# wordclock-ledboard.net
KiCad netlist of a schematic drawn in EAGLE
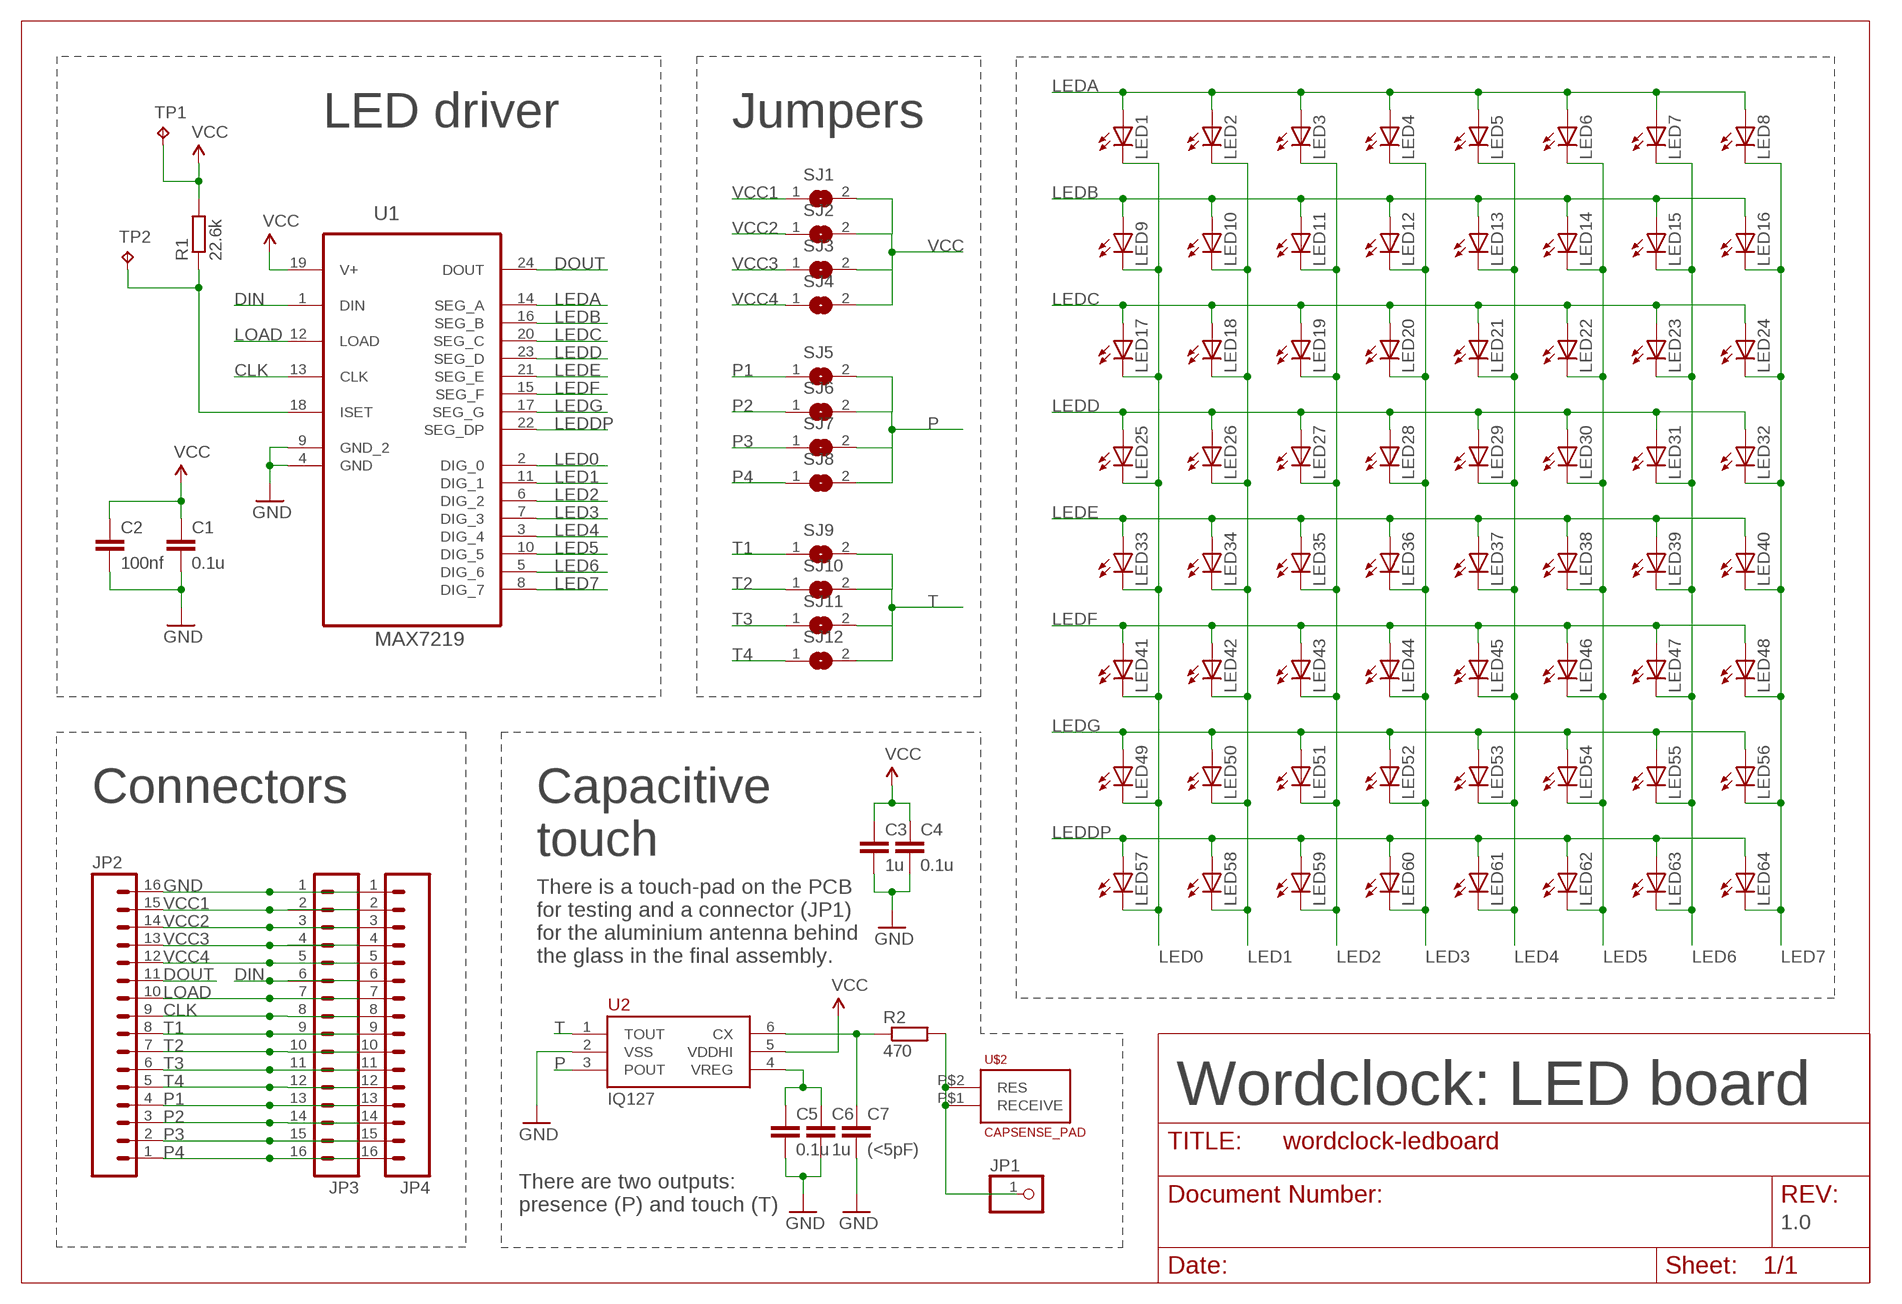
[diagram p0: schematic, sheet 1]

(export (version "E")
  (design (tool "Eeschema 10.0.6"))
  (components
    (comp (ref "C1")
      (value "0.1u")
      (footprint "eagle-import:C0805")
      (libsource (lib "eagle-import") (part "C-EUC0805"))
    )
    (comp (ref "C2")
      (value "100nf")
      (footprint "eagle-import:C0805")
      (libsource (lib "eagle-import") (part "C-EUC0805"))
    )
    (comp (ref "C3")
      (value "1u")
      (footprint "eagle-import:C0805")
      (libsource (lib "eagle-import") (part "C-EUC0805"))
    )
    (comp (ref "C4")
      (value "0.1u")
      (footprint "eagle-import:C0805")
      (libsource (lib "eagle-import") (part "C-EUC0805"))
    )
    (comp (ref "C5")
      (value "0.1u")
      (footprint "eagle-import:C0805")
      (libsource (lib "eagle-import") (part "C-EUC0805"))
    )
    (comp (ref "C6")
      (value "1u")
      (footprint "eagle-import:C0805")
      (libsource (lib "eagle-import") (part "C-EUC0805"))
    )
    (comp (ref "C7")
      (value "(<5pF)")
      (footprint "eagle-import:C0805")
      (libsource (lib "eagle-import") (part "C-EUC0805"))
    )
    (comp (ref "JP1")
      (value "PINHD-1X1")
      (footprint "eagle-import:1X01")
      (libsource (lib "eagle-import") (part "PINHD-1X1"))
    )
    (comp (ref "JP2")
      (value "M161X16_NO_SILK")
      (footprint "eagle-import:1X16_NO_SILK")
      (libsource (lib "eagle-import") (part "M161X16_NO_SILK"))
    )
    (comp (ref "JP3")
      (value "M161X16_NO_SILK")
      (footprint "eagle-import:1X16_NO_SILK")
      (libsource (lib "eagle-import") (part "M161X16_NO_SILK"))
    )
    (comp (ref "JP4")
      (value "M161X16_NO_SILK")
      (footprint "eagle-import:1X16_NO_SILK")
      (libsource (lib "eagle-import") (part "M161X16_NO_SILK"))
    )
    (comp (ref "LED1")
      (value "LEDKA-3528ASYC")
      (footprint "eagle-import:KA-3528ASYC")
      (libsource (lib "eagle-import") (part "LEDKA-3528ASYC"))
    )
    (comp (ref "LED2")
      (value "LEDKA-3528ASYC")
      (footprint "eagle-import:KA-3528ASYC")
      (libsource (lib "eagle-import") (part "LEDKA-3528ASYC"))
    )
    (comp (ref "LED3")
      (value "LEDKA-3528ASYC")
      (footprint "eagle-import:KA-3528ASYC")
      (libsource (lib "eagle-import") (part "LEDKA-3528ASYC"))
    )
    (comp (ref "LED4")
      (value "LEDKA-3528ASYC")
      (footprint "eagle-import:KA-3528ASYC")
      (libsource (lib "eagle-import") (part "LEDKA-3528ASYC"))
    )
    (comp (ref "LED5")
      (value "LEDKA-3528ASYC")
      (footprint "eagle-import:KA-3528ASYC")
      (libsource (lib "eagle-import") (part "LEDKA-3528ASYC"))
    )
    (comp (ref "LED6")
      (value "LEDKA-3528ASYC")
      (footprint "eagle-import:KA-3528ASYC")
      (libsource (lib "eagle-import") (part "LEDKA-3528ASYC"))
    )
    (comp (ref "LED7")
      (value "LEDKA-3528ASYC")
      (footprint "eagle-import:KA-3528ASYC")
      (libsource (lib "eagle-import") (part "LEDKA-3528ASYC"))
    )
    (comp (ref "LED8")
      (value "LEDKA-3528ASYC")
      (footprint "eagle-import:KA-3528ASYC")
      (libsource (lib "eagle-import") (part "LEDKA-3528ASYC"))
    )
    (comp (ref "LED9")
      (value "LEDKA-3528ASYC")
      (footprint "eagle-import:KA-3528ASYC")
      (libsource (lib "eagle-import") (part "LEDKA-3528ASYC"))
    )
    (comp (ref "LED10")
      (value "LEDKA-3528ASYC")
      (footprint "eagle-import:KA-3528ASYC")
      (libsource (lib "eagle-import") (part "LEDKA-3528ASYC"))
    )
    (comp (ref "LED11")
      (value "LEDKA-3528ASYC")
      (footprint "eagle-import:KA-3528ASYC")
      (libsource (lib "eagle-import") (part "LEDKA-3528ASYC"))
    )
    (comp (ref "LED12")
      (value "LEDKA-3528ASYC")
      (footprint "eagle-import:KA-3528ASYC")
      (libsource (lib "eagle-import") (part "LEDKA-3528ASYC"))
    )
    (comp (ref "LED13")
      (value "LEDKA-3528ASYC")
      (footprint "eagle-import:KA-3528ASYC")
      (libsource (lib "eagle-import") (part "LEDKA-3528ASYC"))
    )
    (comp (ref "LED14")
      (value "LEDKA-3528ASYC")
      (footprint "eagle-import:KA-3528ASYC")
      (libsource (lib "eagle-import") (part "LEDKA-3528ASYC"))
    )
    (comp (ref "LED15")
      (value "LEDKA-3528ASYC")
      (footprint "eagle-import:KA-3528ASYC")
      (libsource (lib "eagle-import") (part "LEDKA-3528ASYC"))
    )
    (comp (ref "LED16")
      (value "LEDKA-3528ASYC")
      (footprint "eagle-import:KA-3528ASYC")
      (libsource (lib "eagle-import") (part "LEDKA-3528ASYC"))
    )
    (comp (ref "LED17")
      (value "LEDKA-3528ASYC")
      (footprint "eagle-import:KA-3528ASYC")
      (libsource (lib "eagle-import") (part "LEDKA-3528ASYC"))
    )
    (comp (ref "LED18")
      (value "LEDKA-3528ASYC")
      (footprint "eagle-import:KA-3528ASYC")
      (libsource (lib "eagle-import") (part "LEDKA-3528ASYC"))
    )
    (comp (ref "LED19")
      (value "LEDKA-3528ASYC")
      (footprint "eagle-import:KA-3528ASYC")
      (libsource (lib "eagle-import") (part "LEDKA-3528ASYC"))
    )
    (comp (ref "LED20")
      (value "LEDKA-3528ASYC")
      (footprint "eagle-import:KA-3528ASYC")
      (libsource (lib "eagle-import") (part "LEDKA-3528ASYC"))
    )
    (comp (ref "LED21")
      (value "LEDKA-3528ASYC")
      (footprint "eagle-import:KA-3528ASYC")
      (libsource (lib "eagle-import") (part "LEDKA-3528ASYC"))
    )
    (comp (ref "LED22")
      (value "LEDKA-3528ASYC")
      (footprint "eagle-import:KA-3528ASYC")
      (libsource (lib "eagle-import") (part "LEDKA-3528ASYC"))
    )
    (comp (ref "LED23")
      (value "LEDKA-3528ASYC")
      (footprint "eagle-import:KA-3528ASYC")
      (libsource (lib "eagle-import") (part "LEDKA-3528ASYC"))
    )
    (comp (ref "LED24")
      (value "LEDKA-3528ASYC")
      (footprint "eagle-import:KA-3528ASYC")
      (libsource (lib "eagle-import") (part "LEDKA-3528ASYC"))
    )
    (comp (ref "LED25")
      (value "LEDKA-3528ASYC")
      (footprint "eagle-import:KA-3528ASYC")
      (libsource (lib "eagle-import") (part "LEDKA-3528ASYC"))
    )
    (comp (ref "LED26")
      (value "LEDKA-3528ASYC")
      (footprint "eagle-import:KA-3528ASYC")
      (libsource (lib "eagle-import") (part "LEDKA-3528ASYC"))
    )
    (comp (ref "LED27")
      (value "LEDKA-3528ASYC")
      (footprint "eagle-import:KA-3528ASYC")
      (libsource (lib "eagle-import") (part "LEDKA-3528ASYC"))
    )
    (comp (ref "LED28")
      (value "LEDKA-3528ASYC")
      (footprint "eagle-import:KA-3528ASYC")
      (libsource (lib "eagle-import") (part "LEDKA-3528ASYC"))
    )
    (comp (ref "LED29")
      (value "LEDKA-3528ASYC")
      (footprint "eagle-import:KA-3528ASYC")
      (libsource (lib "eagle-import") (part "LEDKA-3528ASYC"))
    )
    (comp (ref "LED30")
      (value "LEDKA-3528ASYC")
      (footprint "eagle-import:KA-3528ASYC")
      (libsource (lib "eagle-import") (part "LEDKA-3528ASYC"))
    )
    (comp (ref "LED31")
      (value "LEDKA-3528ASYC")
      (footprint "eagle-import:KA-3528ASYC")
      (libsource (lib "eagle-import") (part "LEDKA-3528ASYC"))
    )
    (comp (ref "LED32")
      (value "LEDKA-3528ASYC")
      (footprint "eagle-import:KA-3528ASYC")
      (libsource (lib "eagle-import") (part "LEDKA-3528ASYC"))
    )
    (comp (ref "LED33")
      (value "LEDKA-3528ASYC")
      (footprint "eagle-import:KA-3528ASYC")
      (libsource (lib "eagle-import") (part "LEDKA-3528ASYC"))
    )
    (comp (ref "LED34")
      (value "LEDKA-3528ASYC")
      (footprint "eagle-import:KA-3528ASYC")
      (libsource (lib "eagle-import") (part "LEDKA-3528ASYC"))
    )
    (comp (ref "LED35")
      (value "LEDKA-3528ASYC")
      (footprint "eagle-import:KA-3528ASYC")
      (libsource (lib "eagle-import") (part "LEDKA-3528ASYC"))
    )
    (comp (ref "LED36")
      (value "LEDKA-3528ASYC")
      (footprint "eagle-import:KA-3528ASYC")
      (libsource (lib "eagle-import") (part "LEDKA-3528ASYC"))
    )
    (comp (ref "LED37")
      (value "LEDKA-3528ASYC")
      (footprint "eagle-import:KA-3528ASYC")
      (libsource (lib "eagle-import") (part "LEDKA-3528ASYC"))
    )
    (comp (ref "LED38")
      (value "LEDKA-3528ASYC")
      (footprint "eagle-import:KA-3528ASYC")
      (libsource (lib "eagle-import") (part "LEDKA-3528ASYC"))
    )
    (comp (ref "LED39")
      (value "LEDKA-3528ASYC")
      (footprint "eagle-import:KA-3528ASYC")
      (libsource (lib "eagle-import") (part "LEDKA-3528ASYC"))
    )
    (comp (ref "LED40")
      (value "LEDKA-3528ASYC")
      (footprint "eagle-import:KA-3528ASYC")
      (libsource (lib "eagle-import") (part "LEDKA-3528ASYC"))
    )
    (comp (ref "LED41")
      (value "LEDKA-3528ASYC")
      (footprint "eagle-import:KA-3528ASYC")
      (libsource (lib "eagle-import") (part "LEDKA-3528ASYC"))
    )
    (comp (ref "LED42")
      (value "LEDKA-3528ASYC")
      (footprint "eagle-import:KA-3528ASYC")
      (libsource (lib "eagle-import") (part "LEDKA-3528ASYC"))
    )
    (comp (ref "LED43")
      (value "LEDKA-3528ASYC")
      (footprint "eagle-import:KA-3528ASYC")
      (libsource (lib "eagle-import") (part "LEDKA-3528ASYC"))
    )
    (comp (ref "LED44")
      (value "LEDKA-3528ASYC")
      (footprint "eagle-import:KA-3528ASYC")
      (libsource (lib "eagle-import") (part "LEDKA-3528ASYC"))
    )
    (comp (ref "LED45")
      (value "LEDKA-3528ASYC")
      (footprint "eagle-import:KA-3528ASYC")
      (libsource (lib "eagle-import") (part "LEDKA-3528ASYC"))
    )
    (comp (ref "LED46")
      (value "LEDKA-3528ASYC")
      (footprint "eagle-import:KA-3528ASYC")
      (libsource (lib "eagle-import") (part "LEDKA-3528ASYC"))
    )
    (comp (ref "LED47")
      (value "LEDKA-3528ASYC")
      (footprint "eagle-import:KA-3528ASYC")
      (libsource (lib "eagle-import") (part "LEDKA-3528ASYC"))
    )
    (comp (ref "LED48")
      (value "LEDKA-3528ASYC")
      (footprint "eagle-import:KA-3528ASYC")
      (libsource (lib "eagle-import") (part "LEDKA-3528ASYC"))
    )
    (comp (ref "LED49")
      (value "LEDKA-3528ASYC")
      (footprint "eagle-import:KA-3528ASYC")
      (libsource (lib "eagle-import") (part "LEDKA-3528ASYC"))
    )
    (comp (ref "LED50")
      (value "LEDKA-3528ASYC")
      (footprint "eagle-import:KA-3528ASYC")
      (libsource (lib "eagle-import") (part "LEDKA-3528ASYC"))
    )
    (comp (ref "LED51")
      (value "LEDKA-3528ASYC")
      (footprint "eagle-import:KA-3528ASYC")
      (libsource (lib "eagle-import") (part "LEDKA-3528ASYC"))
    )
    (comp (ref "LED52")
      (value "LEDKA-3528ASYC")
      (footprint "eagle-import:KA-3528ASYC")
      (libsource (lib "eagle-import") (part "LEDKA-3528ASYC"))
    )
    (comp (ref "LED53")
      (value "LEDKA-3528ASYC")
      (footprint "eagle-import:KA-3528ASYC")
      (libsource (lib "eagle-import") (part "LEDKA-3528ASYC"))
    )
    (comp (ref "LED54")
      (value "LEDKA-3528ASYC")
      (footprint "eagle-import:KA-3528ASYC")
      (libsource (lib "eagle-import") (part "LEDKA-3528ASYC"))
    )
    (comp (ref "LED55")
      (value "LEDKA-3528ASYC")
      (footprint "eagle-import:KA-3528ASYC")
      (libsource (lib "eagle-import") (part "LEDKA-3528ASYC"))
    )
    (comp (ref "LED56")
      (value "LEDKA-3528ASYC")
      (footprint "eagle-import:KA-3528ASYC")
      (libsource (lib "eagle-import") (part "LEDKA-3528ASYC"))
    )
    (comp (ref "LED57")
      (value "LEDKA-3528ASYC")
      (footprint "eagle-import:KA-3528ASYC")
      (libsource (lib "eagle-import") (part "LEDKA-3528ASYC"))
    )
    (comp (ref "LED58")
      (value "LEDKA-3528ASYC")
      (footprint "eagle-import:KA-3528ASYC")
      (libsource (lib "eagle-import") (part "LEDKA-3528ASYC"))
    )
    (comp (ref "LED59")
      (value "LEDKA-3528ASYC")
      (footprint "eagle-import:KA-3528ASYC")
      (libsource (lib "eagle-import") (part "LEDKA-3528ASYC"))
    )
    (comp (ref "LED60")
      (value "LEDKA-3528ASYC")
      (footprint "eagle-import:KA-3528ASYC")
      (libsource (lib "eagle-import") (part "LEDKA-3528ASYC"))
    )
    (comp (ref "LED61")
      (value "LEDKA-3528ASYC")
      (footprint "eagle-import:KA-3528ASYC")
      (libsource (lib "eagle-import") (part "LEDKA-3528ASYC"))
    )
    (comp (ref "LED62")
      (value "LEDKA-3528ASYC")
      (footprint "eagle-import:KA-3528ASYC")
      (libsource (lib "eagle-import") (part "LEDKA-3528ASYC"))
    )
    (comp (ref "LED63")
      (value "LEDKA-3528ASYC")
      (footprint "eagle-import:KA-3528ASYC")
      (libsource (lib "eagle-import") (part "LEDKA-3528ASYC"))
    )
    (comp (ref "LED64")
      (value "LEDKA-3528ASYC")
      (footprint "eagle-import:KA-3528ASYC")
      (libsource (lib "eagle-import") (part "LEDKA-3528ASYC"))
    )
    (comp (ref "R1")
      (value "22.6k")
      (footprint "eagle-import:R0603")
      (libsource (lib "eagle-import") (part "R-EU_R0603"))
    )
    (comp (ref "R2")
      (value "470")
      (footprint "eagle-import:R0603")
      (libsource (lib "eagle-import") (part "R-EU_R0603"))
    )
    (comp (ref "SJ1")
      (value "SJW")
      (footprint "eagle-import:SJW")
      (libsource (lib "eagle-import") (part "SJW"))
    )
    (comp (ref "SJ2")
      (value "SJW")
      (footprint "eagle-import:SJW")
      (libsource (lib "eagle-import") (part "SJW"))
    )
    (comp (ref "SJ3")
      (value "SJW")
      (footprint "eagle-import:SJW")
      (libsource (lib "eagle-import") (part "SJW"))
    )
    (comp (ref "SJ4")
      (value "SJW")
      (footprint "eagle-import:SJW")
      (libsource (lib "eagle-import") (part "SJW"))
    )
    (comp (ref "SJ5")
      (value "SJW")
      (footprint "eagle-import:SJW")
      (libsource (lib "eagle-import") (part "SJW"))
    )
    (comp (ref "SJ6")
      (value "SJW")
      (footprint "eagle-import:SJW")
      (libsource (lib "eagle-import") (part "SJW"))
    )
    (comp (ref "SJ7")
      (value "SJW")
      (footprint "eagle-import:SJW")
      (libsource (lib "eagle-import") (part "SJW"))
    )
    (comp (ref "SJ8")
      (value "SJW")
      (footprint "eagle-import:SJW")
      (libsource (lib "eagle-import") (part "SJW"))
    )
    (comp (ref "SJ9")
      (value "SJW")
      (footprint "eagle-import:SJW")
      (libsource (lib "eagle-import") (part "SJW"))
    )
    (comp (ref "SJ10")
      (value "SJW")
      (footprint "eagle-import:SJW")
      (libsource (lib "eagle-import") (part "SJW"))
    )
    (comp (ref "SJ11")
      (value "SJW")
      (footprint "eagle-import:SJW")
      (libsource (lib "eagle-import") (part "SJW"))
    )
    (comp (ref "SJ12")
      (value "SJW")
      (footprint "eagle-import:SJW")
      (libsource (lib "eagle-import") (part "SJW"))
    )
    (comp (ref "TP1")
      (value "TPTP20R")
      (footprint "eagle-import:TP20R")
      (libsource (lib "eagle-import") (part "TPTP20R"))
    )
    (comp (ref "TP2")
      (value "TPTP20R")
      (footprint "eagle-import:TP20R")
      (libsource (lib "eagle-import") (part "TPTP20R"))
    )
    (comp (ref "U$2")
      (value "CAPSENSE_PAD")
      (footprint "eagle-import:CAPSENSE_PAD")
      (libsource (lib "eagle-import") (part "CAPSENSE_PAD"))
    )
    (comp (ref "U1")
      (value "MAX7219")
      (footprint "eagle-import:SOIC127P1032X265-24N")
      (fields (field (name "MPN") "MAX7219CWG+T"))
      (libsource (lib "eagle-import") (part "MAX7219CWG+T"))
    )
    (comp (ref "U2")
      (value "IQ127")
      (footprint "eagle-import:TSOT-23-6")
      (libsource (lib "eagle-import") (part "IQ127"))
    )
  )
  (nets
    (net (code "1") (name "/CLK") (class "Default")
      (node (ref "JP2") (pin "9") (pinfunction "9_9") (pintype "passive"))
      (node (ref "JP3") (pin "8") (pinfunction "8_8") (pintype "passive"))
      (node (ref "JP4") (pin "8") (pinfunction "8_8") (pintype "passive"))
      (node (ref "U1") (pin "13") (pinfunction "CLK_13") (pintype "input"))
    )
    (net (code "2") (name "/DIN") (class "Default")
      (node (ref "JP3") (pin "6") (pinfunction "6_6") (pintype "passive"))
      (node (ref "JP4") (pin "6") (pinfunction "6_6") (pintype "passive"))
      (node (ref "U1") (pin "1") (pinfunction "DIN_1") (pintype "input"))
    )
    (net (code "3") (name "/DOUT") (class "Default")
      (node (ref "JP2") (pin "11") (pinfunction "11_11") (pintype "passive"))
      (node (ref "U1") (pin "24") (pinfunction "DOUT_24") (pintype "output"))
    )
    (net (code "4") (name "/LED0") (class "Default")
      (node (ref "LED1") (pin "C") (pinfunction "C_C") (pintype "passive"))
      (node (ref "LED17") (pin "C") (pinfunction "C_C") (pintype "passive"))
      (node (ref "LED25") (pin "C") (pinfunction "C_C") (pintype "passive"))
      (node (ref "LED33") (pin "C") (pinfunction "C_C") (pintype "passive"))
      (node (ref "LED41") (pin "C") (pinfunction "C_C") (pintype "passive"))
      (node (ref "LED49") (pin "C") (pinfunction "C_C") (pintype "passive"))
      (node (ref "LED57") (pin "C") (pinfunction "C_C") (pintype "passive"))
      (node (ref "LED9") (pin "C") (pinfunction "C_C") (pintype "passive"))
      (node (ref "U1") (pin "2") (pinfunction "DIG_0_2") (pintype "output"))
    )
    (net (code "5") (name "/LED1") (class "Default")
      (node (ref "LED10") (pin "C") (pinfunction "C_C") (pintype "passive"))
      (node (ref "LED18") (pin "C") (pinfunction "C_C") (pintype "passive"))
      (node (ref "LED2") (pin "C") (pinfunction "C_C") (pintype "passive"))
      (node (ref "LED26") (pin "C") (pinfunction "C_C") (pintype "passive"))
      (node (ref "LED34") (pin "C") (pinfunction "C_C") (pintype "passive"))
      (node (ref "LED42") (pin "C") (pinfunction "C_C") (pintype "passive"))
      (node (ref "LED50") (pin "C") (pinfunction "C_C") (pintype "passive"))
      (node (ref "LED58") (pin "C") (pinfunction "C_C") (pintype "passive"))
      (node (ref "U1") (pin "11") (pinfunction "DIG_1_11") (pintype "output"))
    )
    (net (code "6") (name "/LED2") (class "Default")
      (node (ref "LED11") (pin "C") (pinfunction "C_C") (pintype "passive"))
      (node (ref "LED19") (pin "C") (pinfunction "C_C") (pintype "passive"))
      (node (ref "LED27") (pin "C") (pinfunction "C_C") (pintype "passive"))
      (node (ref "LED3") (pin "C") (pinfunction "C_C") (pintype "passive"))
      (node (ref "LED35") (pin "C") (pinfunction "C_C") (pintype "passive"))
      (node (ref "LED43") (pin "C") (pinfunction "C_C") (pintype "passive"))
      (node (ref "LED51") (pin "C") (pinfunction "C_C") (pintype "passive"))
      (node (ref "LED59") (pin "C") (pinfunction "C_C") (pintype "passive"))
      (node (ref "U1") (pin "6") (pinfunction "DIG_2_6") (pintype "output"))
    )
    (net (code "7") (name "/LED3") (class "Default")
      (node (ref "LED12") (pin "C") (pinfunction "C_C") (pintype "passive"))
      (node (ref "LED20") (pin "C") (pinfunction "C_C") (pintype "passive"))
      (node (ref "LED28") (pin "C") (pinfunction "C_C") (pintype "passive"))
      (node (ref "LED36") (pin "C") (pinfunction "C_C") (pintype "passive"))
      (node (ref "LED4") (pin "C") (pinfunction "C_C") (pintype "passive"))
      (node (ref "LED44") (pin "C") (pinfunction "C_C") (pintype "passive"))
      (node (ref "LED52") (pin "C") (pinfunction "C_C") (pintype "passive"))
      (node (ref "LED60") (pin "C") (pinfunction "C_C") (pintype "passive"))
      (node (ref "U1") (pin "7") (pinfunction "DIG_3_7") (pintype "output"))
    )
    (net (code "8") (name "/LED4") (class "Default")
      (node (ref "LED13") (pin "C") (pinfunction "C_C") (pintype "passive"))
      (node (ref "LED21") (pin "C") (pinfunction "C_C") (pintype "passive"))
      (node (ref "LED29") (pin "C") (pinfunction "C_C") (pintype "passive"))
      (node (ref "LED37") (pin "C") (pinfunction "C_C") (pintype "passive"))
      (node (ref "LED45") (pin "C") (pinfunction "C_C") (pintype "passive"))
      (node (ref "LED5") (pin "C") (pinfunction "C_C") (pintype "passive"))
      (node (ref "LED53") (pin "C") (pinfunction "C_C") (pintype "passive"))
      (node (ref "LED61") (pin "C") (pinfunction "C_C") (pintype "passive"))
      (node (ref "U1") (pin "3") (pinfunction "DIG_4_3") (pintype "output"))
    )
    (net (code "9") (name "/LED5") (class "Default")
      (node (ref "LED14") (pin "C") (pinfunction "C_C") (pintype "passive"))
      (node (ref "LED22") (pin "C") (pinfunction "C_C") (pintype "passive"))
      (node (ref "LED30") (pin "C") (pinfunction "C_C") (pintype "passive"))
      (node (ref "LED38") (pin "C") (pinfunction "C_C") (pintype "passive"))
      (node (ref "LED46") (pin "C") (pinfunction "C_C") (pintype "passive"))
      (node (ref "LED54") (pin "C") (pinfunction "C_C") (pintype "passive"))
      (node (ref "LED6") (pin "C") (pinfunction "C_C") (pintype "passive"))
      (node (ref "LED62") (pin "C") (pinfunction "C_C") (pintype "passive"))
      (node (ref "U1") (pin "10") (pinfunction "DIG_5_10") (pintype "output"))
    )
    (net (code "10") (name "/LED6") (class "Default")
      (node (ref "LED15") (pin "C") (pinfunction "C_C") (pintype "passive"))
      (node (ref "LED23") (pin "C") (pinfunction "C_C") (pintype "passive"))
      (node (ref "LED31") (pin "C") (pinfunction "C_C") (pintype "passive"))
      (node (ref "LED39") (pin "C") (pinfunction "C_C") (pintype "passive"))
      (node (ref "LED47") (pin "C") (pinfunction "C_C") (pintype "passive"))
      (node (ref "LED55") (pin "C") (pinfunction "C_C") (pintype "passive"))
      (node (ref "LED63") (pin "C") (pinfunction "C_C") (pintype "passive"))
      (node (ref "LED7") (pin "C") (pinfunction "C_C") (pintype "passive"))
      (node (ref "U1") (pin "5") (pinfunction "DIG_6_5") (pintype "output"))
    )
    (net (code "11") (name "/LED7") (class "Default")
      (node (ref "LED16") (pin "C") (pinfunction "C_C") (pintype "passive"))
      (node (ref "LED24") (pin "C") (pinfunction "C_C") (pintype "passive"))
      (node (ref "LED32") (pin "C") (pinfunction "C_C") (pintype "passive"))
      (node (ref "LED40") (pin "C") (pinfunction "C_C") (pintype "passive"))
      (node (ref "LED48") (pin "C") (pinfunction "C_C") (pintype "passive"))
      (node (ref "LED56") (pin "C") (pinfunction "C_C") (pintype "passive"))
      (node (ref "LED64") (pin "C") (pinfunction "C_C") (pintype "passive"))
      (node (ref "LED8") (pin "C") (pinfunction "C_C") (pintype "passive"))
      (node (ref "U1") (pin "8") (pinfunction "DIG_7_8") (pintype "output"))
    )
    (net (code "12") (name "/LEDA") (class "Default")
      (node (ref "LED1") (pin "A") (pinfunction "A_A") (pintype "passive"))
      (node (ref "LED2") (pin "A") (pinfunction "A_A") (pintype "passive"))
      (node (ref "LED3") (pin "A") (pinfunction "A_A") (pintype "passive"))
      (node (ref "LED4") (pin "A") (pinfunction "A_A") (pintype "passive"))
      (node (ref "LED5") (pin "A") (pinfunction "A_A") (pintype "passive"))
      (node (ref "LED6") (pin "A") (pinfunction "A_A") (pintype "passive"))
      (node (ref "LED7") (pin "A") (pinfunction "A_A") (pintype "passive"))
      (node (ref "LED8") (pin "A") (pinfunction "A_A") (pintype "passive"))
      (node (ref "U1") (pin "14") (pinfunction "SEG_A_14") (pintype "output"))
    )
    (net (code "13") (name "/LEDB") (class "Default")
      (node (ref "LED10") (pin "A") (pinfunction "A_A") (pintype "passive"))
      (node (ref "LED11") (pin "A") (pinfunction "A_A") (pintype "passive"))
      (node (ref "LED12") (pin "A") (pinfunction "A_A") (pintype "passive"))
      (node (ref "LED13") (pin "A") (pinfunction "A_A") (pintype "passive"))
      (node (ref "LED14") (pin "A") (pinfunction "A_A") (pintype "passive"))
      (node (ref "LED15") (pin "A") (pinfunction "A_A") (pintype "passive"))
      (node (ref "LED16") (pin "A") (pinfunction "A_A") (pintype "passive"))
      (node (ref "LED9") (pin "A") (pinfunction "A_A") (pintype "passive"))
      (node (ref "U1") (pin "16") (pinfunction "SEG_B_16") (pintype "output"))
    )
    (net (code "14") (name "/LEDC") (class "Default")
      (node (ref "LED17") (pin "A") (pinfunction "A_A") (pintype "passive"))
      (node (ref "LED18") (pin "A") (pinfunction "A_A") (pintype "passive"))
      (node (ref "LED19") (pin "A") (pinfunction "A_A") (pintype "passive"))
      (node (ref "LED20") (pin "A") (pinfunction "A_A") (pintype "passive"))
      (node (ref "LED21") (pin "A") (pinfunction "A_A") (pintype "passive"))
      (node (ref "LED22") (pin "A") (pinfunction "A_A") (pintype "passive"))
      (node (ref "LED23") (pin "A") (pinfunction "A_A") (pintype "passive"))
      (node (ref "LED24") (pin "A") (pinfunction "A_A") (pintype "passive"))
      (node (ref "U1") (pin "20") (pinfunction "SEG_C_20") (pintype "output"))
    )
    (net (code "15") (name "/LEDD") (class "Default")
      (node (ref "LED25") (pin "A") (pinfunction "A_A") (pintype "passive"))
      (node (ref "LED26") (pin "A") (pinfunction "A_A") (pintype "passive"))
      (node (ref "LED27") (pin "A") (pinfunction "A_A") (pintype "passive"))
      (node (ref "LED28") (pin "A") (pinfunction "A_A") (pintype "passive"))
      (node (ref "LED29") (pin "A") (pinfunction "A_A") (pintype "passive"))
      (node (ref "LED30") (pin "A") (pinfunction "A_A") (pintype "passive"))
      (node (ref "LED31") (pin "A") (pinfunction "A_A") (pintype "passive"))
      (node (ref "LED32") (pin "A") (pinfunction "A_A") (pintype "passive"))
      (node (ref "U1") (pin "23") (pinfunction "SEG_D_23") (pintype "output"))
    )
    (net (code "16") (name "/LEDDP") (class "Default")
      (node (ref "LED57") (pin "A") (pinfunction "A_A") (pintype "passive"))
      (node (ref "LED58") (pin "A") (pinfunction "A_A") (pintype "passive"))
      (node (ref "LED59") (pin "A") (pinfunction "A_A") (pintype "passive"))
      (node (ref "LED60") (pin "A") (pinfunction "A_A") (pintype "passive"))
      (node (ref "LED61") (pin "A") (pinfunction "A_A") (pintype "passive"))
      (node (ref "LED62") (pin "A") (pinfunction "A_A") (pintype "passive"))
      (node (ref "LED63") (pin "A") (pinfunction "A_A") (pintype "passive"))
      (node (ref "LED64") (pin "A") (pinfunction "A_A") (pintype "passive"))
      (node (ref "U1") (pin "22") (pinfunction "SEG_DP_22") (pintype "output"))
    )
    (net (code "17") (name "/LEDE") (class "Default")
      (node (ref "LED33") (pin "A") (pinfunction "A_A") (pintype "passive"))
      (node (ref "LED34") (pin "A") (pinfunction "A_A") (pintype "passive"))
      (node (ref "LED35") (pin "A") (pinfunction "A_A") (pintype "passive"))
      (node (ref "LED36") (pin "A") (pinfunction "A_A") (pintype "passive"))
      (node (ref "LED37") (pin "A") (pinfunction "A_A") (pintype "passive"))
      (node (ref "LED38") (pin "A") (pinfunction "A_A") (pintype "passive"))
      (node (ref "LED39") (pin "A") (pinfunction "A_A") (pintype "passive"))
      (node (ref "LED40") (pin "A") (pinfunction "A_A") (pintype "passive"))
      (node (ref "U1") (pin "21") (pinfunction "SEG_E_21") (pintype "output"))
    )
    (net (code "18") (name "/LEDF") (class "Default")
      (node (ref "LED41") (pin "A") (pinfunction "A_A") (pintype "passive"))
      (node (ref "LED42") (pin "A") (pinfunction "A_A") (pintype "passive"))
      (node (ref "LED43") (pin "A") (pinfunction "A_A") (pintype "passive"))
      (node (ref "LED44") (pin "A") (pinfunction "A_A") (pintype "passive"))
      (node (ref "LED45") (pin "A") (pinfunction "A_A") (pintype "passive"))
      (node (ref "LED46") (pin "A") (pinfunction "A_A") (pintype "passive"))
      (node (ref "LED47") (pin "A") (pinfunction "A_A") (pintype "passive"))
      (node (ref "LED48") (pin "A") (pinfunction "A_A") (pintype "passive"))
      (node (ref "U1") (pin "15") (pinfunction "SEG_F_15") (pintype "output"))
    )
    (net (code "19") (name "/LEDG") (class "Default")
      (node (ref "LED49") (pin "A") (pinfunction "A_A") (pintype "passive"))
      (node (ref "LED50") (pin "A") (pinfunction "A_A") (pintype "passive"))
      (node (ref "LED51") (pin "A") (pinfunction "A_A") (pintype "passive"))
      (node (ref "LED52") (pin "A") (pinfunction "A_A") (pintype "passive"))
      (node (ref "LED53") (pin "A") (pinfunction "A_A") (pintype "passive"))
      (node (ref "LED54") (pin "A") (pinfunction "A_A") (pintype "passive"))
      (node (ref "LED55") (pin "A") (pinfunction "A_A") (pintype "passive"))
      (node (ref "LED56") (pin "A") (pinfunction "A_A") (pintype "passive"))
      (node (ref "U1") (pin "17") (pinfunction "SEG_G_17") (pintype "output"))
    )
    (net (code "20") (name "/LOAD") (class "Default")
      (node (ref "JP2") (pin "10") (pinfunction "10_10") (pintype "passive"))
      (node (ref "JP3") (pin "7") (pinfunction "7_7") (pintype "passive"))
      (node (ref "JP4") (pin "7") (pinfunction "7_7") (pintype "passive"))
      (node (ref "U1") (pin "12") (pinfunction "LOAD_12") (pintype "input"))
    )
    (net (code "21") (name "/P") (class "Default")
      (node (ref "SJ5") (pin "2") (pinfunction "2_2") (pintype "passive"))
      (node (ref "SJ6") (pin "2") (pinfunction "2_2") (pintype "passive"))
      (node (ref "SJ7") (pin "2") (pinfunction "2_2") (pintype "passive"))
      (node (ref "SJ8") (pin "2") (pinfunction "2_2") (pintype "passive"))
      (node (ref "U2") (pin "3") (pinfunction "POUT_3") (pintype "bidirectional"))
    )
    (net (code "22") (name "/P1") (class "Default")
      (node (ref "JP2") (pin "4") (pinfunction "4_4") (pintype "passive"))
      (node (ref "JP3") (pin "13") (pinfunction "13_13") (pintype "passive"))
      (node (ref "JP4") (pin "13") (pinfunction "13_13") (pintype "passive"))
      (node (ref "SJ5") (pin "1") (pinfunction "1_1") (pintype "passive"))
    )
    (net (code "23") (name "/P2") (class "Default")
      (node (ref "JP2") (pin "3") (pinfunction "3_3") (pintype "passive"))
      (node (ref "JP3") (pin "14") (pinfunction "14_14") (pintype "passive"))
      (node (ref "JP4") (pin "14") (pinfunction "14_14") (pintype "passive"))
      (node (ref "SJ6") (pin "1") (pinfunction "1_1") (pintype "passive"))
    )
    (net (code "24") (name "/P3") (class "Default")
      (node (ref "JP2") (pin "2") (pinfunction "2_2") (pintype "passive"))
      (node (ref "JP3") (pin "15") (pinfunction "15_15") (pintype "passive"))
      (node (ref "JP4") (pin "15") (pinfunction "15_15") (pintype "passive"))
      (node (ref "SJ7") (pin "1") (pinfunction "1_1") (pintype "passive"))
    )
    (net (code "25") (name "/P4") (class "Default")
      (node (ref "JP2") (pin "1") (pinfunction "1_1") (pintype "passive"))
      (node (ref "JP3") (pin "16") (pinfunction "16_16") (pintype "passive"))
      (node (ref "JP4") (pin "16") (pinfunction "16_16") (pintype "passive"))
      (node (ref "SJ8") (pin "1") (pinfunction "1_1") (pintype "passive"))
    )
    (net (code "26") (name "/T") (class "Default")
      (node (ref "SJ10") (pin "2") (pinfunction "2_2") (pintype "passive"))
      (node (ref "SJ11") (pin "2") (pinfunction "2_2") (pintype "passive"))
      (node (ref "SJ12") (pin "2") (pinfunction "2_2") (pintype "passive"))
      (node (ref "SJ9") (pin "2") (pinfunction "2_2") (pintype "passive"))
      (node (ref "U2") (pin "1") (pinfunction "TOUT_1") (pintype "bidirectional"))
    )
    (net (code "27") (name "/T1") (class "Default")
      (node (ref "JP2") (pin "8") (pinfunction "8_8") (pintype "passive"))
      (node (ref "JP3") (pin "9") (pinfunction "9_9") (pintype "passive"))
      (node (ref "JP4") (pin "9") (pinfunction "9_9") (pintype "passive"))
      (node (ref "SJ9") (pin "1") (pinfunction "1_1") (pintype "passive"))
    )
    (net (code "28") (name "/T2") (class "Default")
      (node (ref "JP2") (pin "7") (pinfunction "7_7") (pintype "passive"))
      (node (ref "JP3") (pin "10") (pinfunction "10_10") (pintype "passive"))
      (node (ref "JP4") (pin "10") (pinfunction "10_10") (pintype "passive"))
      (node (ref "SJ10") (pin "1") (pinfunction "1_1") (pintype "passive"))
    )
    (net (code "29") (name "/T3") (class "Default")
      (node (ref "JP2") (pin "6") (pinfunction "6_6") (pintype "passive"))
      (node (ref "JP3") (pin "11") (pinfunction "11_11") (pintype "passive"))
      (node (ref "JP4") (pin "11") (pinfunction "11_11") (pintype "passive"))
      (node (ref "SJ11") (pin "1") (pinfunction "1_1") (pintype "passive"))
    )
    (net (code "30") (name "/T4") (class "Default")
      (node (ref "JP2") (pin "5") (pinfunction "5_5") (pintype "passive"))
      (node (ref "JP3") (pin "12") (pinfunction "12_12") (pintype "passive"))
      (node (ref "JP4") (pin "12") (pinfunction "12_12") (pintype "passive"))
      (node (ref "SJ12") (pin "1") (pinfunction "1_1") (pintype "passive"))
    )
    (net (code "31") (name "/VCC1") (class "Default")
      (node (ref "JP2") (pin "15") (pinfunction "15_15") (pintype "passive"))
      (node (ref "JP3") (pin "2") (pinfunction "2_2") (pintype "passive"))
      (node (ref "JP4") (pin "2") (pinfunction "2_2") (pintype "passive"))
      (node (ref "SJ1") (pin "1") (pinfunction "1_1") (pintype "passive"))
    )
    (net (code "32") (name "/VCC2") (class "Default")
      (node (ref "JP2") (pin "14") (pinfunction "14_14") (pintype "passive"))
      (node (ref "JP3") (pin "3") (pinfunction "3_3") (pintype "passive"))
      (node (ref "JP4") (pin "3") (pinfunction "3_3") (pintype "passive"))
      (node (ref "SJ2") (pin "1") (pinfunction "1_1") (pintype "passive"))
    )
    (net (code "33") (name "/VCC3") (class "Default")
      (node (ref "JP2") (pin "13") (pinfunction "13_13") (pintype "passive"))
      (node (ref "JP3") (pin "4") (pinfunction "4_4") (pintype "passive"))
      (node (ref "JP4") (pin "4") (pinfunction "4_4") (pintype "passive"))
      (node (ref "SJ3") (pin "1") (pinfunction "1_1") (pintype "passive"))
    )
    (net (code "34") (name "/VCC4") (class "Default")
      (node (ref "JP2") (pin "12") (pinfunction "12_12") (pintype "passive"))
      (node (ref "JP3") (pin "5") (pinfunction "5_5") (pintype "passive"))
      (node (ref "JP4") (pin "5") (pinfunction "5_5") (pintype "passive"))
      (node (ref "SJ4") (pin "1") (pinfunction "1_1") (pintype "passive"))
    )
    (net (code "35") (name "GND") (class "Default")
      (node (ref "C1") (pin "2") (pinfunction "2_2") (pintype "passive"))
      (node (ref "C2") (pin "2") (pinfunction "2_2") (pintype "passive"))
      (node (ref "C3") (pin "2") (pinfunction "2_2") (pintype "passive"))
      (node (ref "C4") (pin "2") (pinfunction "2_2") (pintype "passive"))
      (node (ref "C5") (pin "2") (pinfunction "2_2") (pintype "passive"))
      (node (ref "C6") (pin "2") (pinfunction "2_2") (pintype "passive"))
      (node (ref "C7") (pin "2") (pinfunction "2_2") (pintype "passive"))
      (node (ref "JP2") (pin "16") (pinfunction "16_16") (pintype "passive"))
      (node (ref "JP3") (pin "1") (pinfunction "1_1") (pintype "passive"))
      (node (ref "JP4") (pin "1") (pinfunction "1_1") (pintype "passive"))
      (node (ref "U1") (pin "4") (pinfunction "GND_4") (pintype "passive"))
      (node (ref "U1") (pin "9") (pinfunction "GND_2_9") (pintype "passive"))
      (node (ref "U2") (pin "2") (pinfunction "VSS_2") (pintype "bidirectional"))
    )
    (net (code "36") (name "Net-(U$2-RECEIVE)") (class "Default")
      (node (ref "JP1") (pin "1") (pinfunction "1_1") (pintype "passive"))
      (node (ref "R2") (pin "2") (pinfunction "2_2") (pintype "passive"))
      (node (ref "U$2") (pin "P$1") (pinfunction "RECEIVE_P$1") (pintype "bidirectional"))
      (node (ref "U$2") (pin "P$2") (pinfunction "RES_P$2") (pintype "bidirectional"))
    )
    (net (code "37") (name "Net-(U1-ISET)") (class "Default")
      (node (ref "R1") (pin "1") (pinfunction "1_1") (pintype "passive"))
      (node (ref "TP2") (pin "TP") (pinfunction "TP_TP") (pintype "input"))
      (node (ref "U1") (pin "18") (pinfunction "ISET_18") (pintype "input"))
    )
    (net (code "38") (name "Net-(U2-CX)") (class "Default")
      (node (ref "C7") (pin "1") (pinfunction "1_1") (pintype "passive"))
      (node (ref "R2") (pin "1") (pinfunction "1_1") (pintype "passive"))
      (node (ref "U2") (pin "6") (pinfunction "CX_6") (pintype "bidirectional"))
    )
    (net (code "39") (name "Net-(U2-VREG)") (class "Default")
      (node (ref "C5") (pin "1") (pinfunction "1_1") (pintype "passive"))
      (node (ref "C6") (pin "1") (pinfunction "1_1") (pintype "passive"))
      (node (ref "U2") (pin "4") (pinfunction "VREG_4") (pintype "bidirectional"))
    )
    (net (code "40") (name "VCC") (class "Default")
      (node (ref "C1") (pin "1") (pinfunction "1_1") (pintype "passive"))
      (node (ref "C2") (pin "1") (pinfunction "1_1") (pintype "passive"))
      (node (ref "C3") (pin "1") (pinfunction "1_1") (pintype "passive"))
      (node (ref "C4") (pin "1") (pinfunction "1_1") (pintype "passive"))
      (node (ref "R1") (pin "2") (pinfunction "2_2") (pintype "passive"))
      (node (ref "SJ1") (pin "2") (pinfunction "2_2") (pintype "passive"))
      (node (ref "SJ2") (pin "2") (pinfunction "2_2") (pintype "passive"))
      (node (ref "SJ3") (pin "2") (pinfunction "2_2") (pintype "passive"))
      (node (ref "SJ4") (pin "2") (pinfunction "2_2") (pintype "passive"))
      (node (ref "TP1") (pin "TP") (pinfunction "TP_TP") (pintype "input"))
      (node (ref "U1") (pin "19") (pinfunction "V+_19") (pintype "power_in"))
      (node (ref "U2") (pin "5") (pinfunction "VDDHI_5") (pintype "bidirectional"))
    )
  )
)
